# LED.net
KiCad netlist of a schematic drawn in Altium Designer
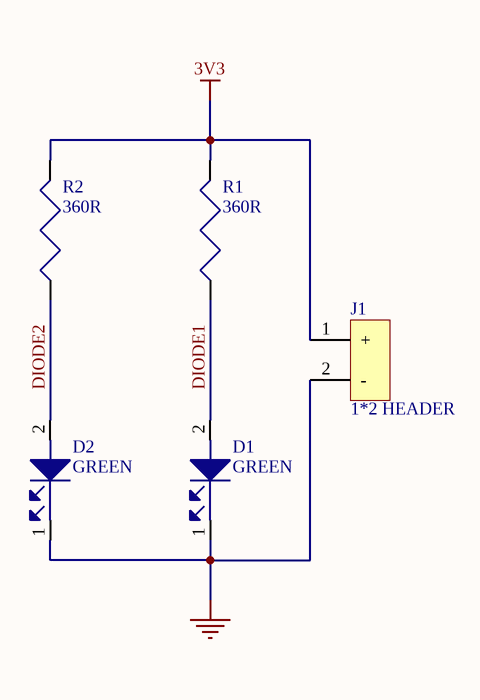
[diagram p0: LED.SchDoc]

(export (version "E")
  (design (tool "Eeschema 10.0.6"))
  (components
    (comp (ref "D1")
      (value "GREEN")
      (footprint "LED0603G")
      (description "Standard LEDs - SMD WL-SMCD SMD MonoChip 0603 BrtGrn 575nm")
      (fields
        (field (name "MANUFACTURER") "Wurth Elektronik")
        (field (name "MANUFACTURER PART NUMBER") "150060VS55040")
      )
      (libsource (lib "LED_Schlib") (part "150060VS55040"))
    )
    (comp (ref "D2")
      (value "GREEN")
      (footprint "LED0603G")
      (description "Standard LEDs - SMD WL-SMCD SMD MonoChip 0603 BrtGrn 575nm")
      (fields
        (field (name "MANUFACTURER") "Wurth Elektronik")
        (field (name "MANUFACTURER PART NUMBER") "150060VS55040")
      )
      (libsource (lib "LED_Schlib") (part "150060VS55040"))
    )
    (comp (ref "J1")
      (value "1*2 HEADER")
      (footprint "HEADER1X2")
      (description "Headers & Wire Housings KK 100 Hdr FrLk Vert 02 Ckt Gold")
      (fields (field (name "MANUFACTURER") "Molex") (field (name "MANUFACTURER PART NUMBER") "22-11-2026"))
      (libsource (lib "LED_Schlib") (part "22-11-2026"))
    )
    (comp (ref "R1")
      (value "360R")
      (footprint "R0805")
      (description "Thick Film Resistors - SMD 360ohm 5%")
      (fields
        (field (name "MANUFACTURER") "Bourns")
        (field (name "MANUFACTURER PART NUMBER") "CR0805-JW-361ELF")
      )
      (libsource (lib "LED_Schlib") (part "CR0805-JW-361ELF"))
    )
    (comp (ref "R2")
      (value "360R")
      (footprint "R0805")
      (description "Thick Film Resistors - SMD 360ohm 5%")
      (fields
        (field (name "MANUFACTURER") "Bourns")
        (field (name "MANUFACTURER PART NUMBER") "CR0805-JW-361ELF")
      )
      (libsource (lib "LED_Schlib") (part "CR0805-JW-361ELF"))
    )
  )
  (nets
    (net (code "1") (name "/DIODE1") (class "Default")
      (node (ref "D1") (pin "2") (pinfunction "2_2") (pintype "passive"))
      (node (ref "R1") (pin "1") (pinfunction "1_1") (pintype "passive"))
    )
    (net (code "2") (name "/DIODE2") (class "Default")
      (node (ref "D2") (pin "2") (pinfunction "2_2") (pintype "passive"))
      (node (ref "R2") (pin "1") (pinfunction "1_1") (pintype "passive"))
    )
    (net (code "3") (name "3V3") (class "Default")
      (node (ref "J1") (pin "1") (pinfunction "+_1") (pintype "passive"))
      (node (ref "R1") (pin "2") (pinfunction "2_2") (pintype "passive"))
      (node (ref "R2") (pin "2") (pinfunction "2_2") (pintype "passive"))
    )
    (net (code "4") (name "GND") (class "Default")
      (node (ref "D1") (pin "1") (pinfunction "1_1") (pintype "passive"))
      (node (ref "D2") (pin "1") (pinfunction "1_1") (pintype "passive"))
      (node (ref "J1") (pin "2") (pinfunction "-_2") (pintype "passive"))
    )
  )
)
